# 3_NET_schdoc.net
KiCad netlist of a schematic drawn in Altium Designer
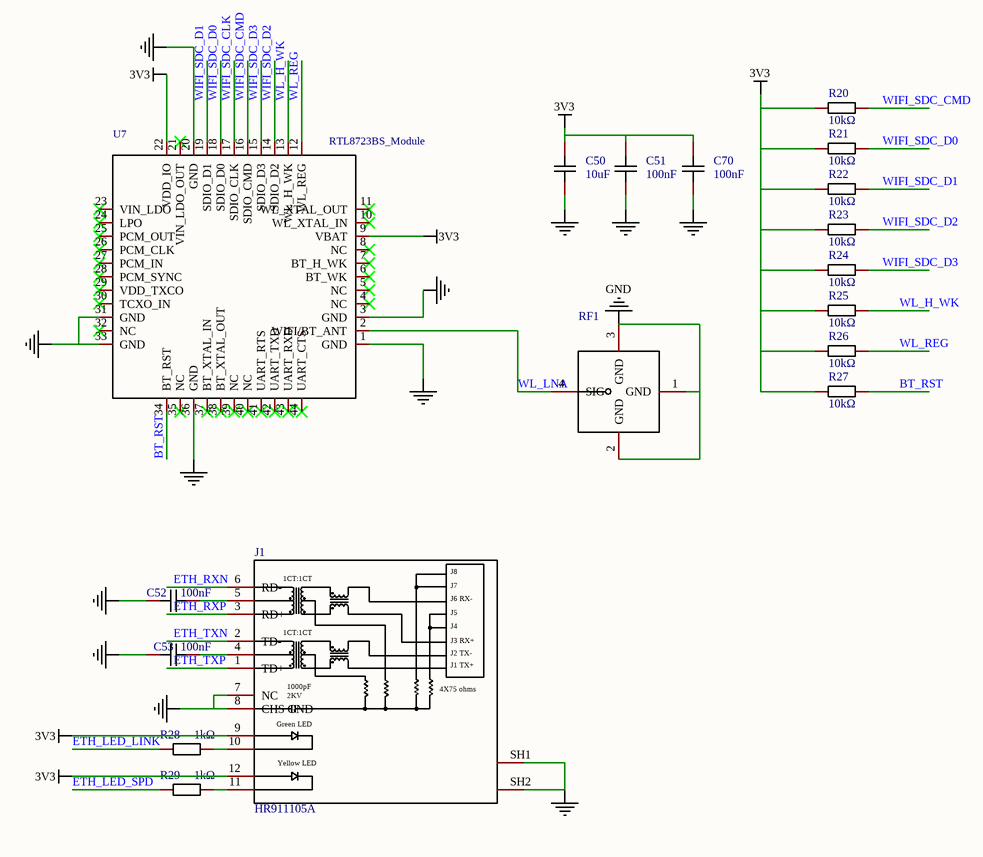
[diagram p0: 3_NET.schdoc.schdoc]

(export (version "E")
  (design (tool "Eeschema 10.0.6"))
  (components
    (comp (ref "C50")
      (value "10uF")
      (fields
        (field (name "NAME") "10uF")
        (field (name "MANUFACTURER") "SAMSUNG(三星)")
        (field (name "MANUFACTURER PART") "CL10A106KP8NNNC")
        (field (name "TOLERANCE") "±10%")
      )
      (libsource (lib "altium-import") (part "root_1_CL10A106KP8NNNC_"))
    )
    (comp (ref "C51")
      (value "100nF")
      (fields
        (field (name "NAME") "100nF")
        (field (name "MANUFACTURER") "YAGEO(国巨)")
        (field (name "MANUFACTURER PART") "CC0603KRX7R9BB104")
        (field (name "TOLERANCE") "±10%")
      )
      (libsource (lib "altium-import") (part "root_1_CC0603KRX7R9BB104_"))
    )
    (comp (ref "C52")
      (value "100nF")
      (fields
        (field (name "NAME") "100nF")
        (field (name "MANUFACTURER") "YAGEO(国巨)")
        (field (name "MANUFACTURER PART") "CC0603KRX7R9BB104")
        (field (name "TOLERANCE") "±10%")
      )
      (libsource (lib "altium-import") (part "root_0_CC0603KRX7R9BB104_"))
    )
    (comp (ref "C53")
      (value "100nF")
      (fields
        (field (name "NAME") "100nF")
        (field (name "MANUFACTURER") "YAGEO(国巨)")
        (field (name "MANUFACTURER PART") "CC0603KRX7R9BB104")
        (field (name "TOLERANCE") "±10%")
      )
      (libsource (lib "altium-import") (part "root_0_CC0603KRX7R9BB104_"))
    )
    (comp (ref "C70")
      (value "100nF")
      (fields
        (field (name "NAME") "100nF")
        (field (name "MANUFACTURER") "YAGEO(国巨)")
        (field (name "MANUFACTURER PART") "CC0603KRX7R9BB104")
        (field (name "TOLERANCE") "±10%")
      )
      (libsource (lib "altium-import") (part "root_1_CC0603KRX7R9BB104_"))
    )
    (comp (ref "J1")
      (value "HR911105A")
      (description "连接器类型:RJ插座;USOC代码:RJ45;端口数量:1;等级:-;屏蔽:-;LED:带LED;")
      (fields (field (name "NAME") "HR911105A") (field (name "MANUFACTURER") "HANRUN(汉仁)"))
      (libsource (lib "altium-import") (part "root_0_HR911105A_C12074_"))
    )
    (comp (ref "R20")
      (value "10kΩ")
      (fields
        (field (name "NAME") "10kΩ")
        (field (name "MANUFACTURER") "UNI-ROYAL(厚声)")
        (field (name "MANUFACTURER PART") "0603WAF1002T5E")
        (field (name "TOLERANCE") "±1%")
      )
      (libsource (lib "altium-import") (part "root_2_0603WAF1002T5E_"))
    )
    (comp (ref "R21")
      (value "10kΩ")
      (fields
        (field (name "NAME") "10kΩ")
        (field (name "MANUFACTURER") "UNI-ROYAL(厚声)")
        (field (name "MANUFACTURER PART") "0603WAF1002T5E")
        (field (name "TOLERANCE") "±1%")
      )
      (libsource (lib "altium-import") (part "root_2_0603WAF1002T5E_"))
    )
    (comp (ref "R22")
      (value "10kΩ")
      (fields
        (field (name "NAME") "10kΩ")
        (field (name "MANUFACTURER") "UNI-ROYAL(厚声)")
        (field (name "MANUFACTURER PART") "0603WAF1002T5E")
        (field (name "TOLERANCE") "±1%")
      )
      (libsource (lib "altium-import") (part "root_2_0603WAF1002T5E_"))
    )
    (comp (ref "R23")
      (value "10kΩ")
      (fields
        (field (name "NAME") "10kΩ")
        (field (name "MANUFACTURER") "UNI-ROYAL(厚声)")
        (field (name "MANUFACTURER PART") "0603WAF1002T5E")
        (field (name "TOLERANCE") "±1%")
      )
      (libsource (lib "altium-import") (part "root_2_0603WAF1002T5E_"))
    )
    (comp (ref "R24")
      (value "10kΩ")
      (fields
        (field (name "NAME") "10kΩ")
        (field (name "MANUFACTURER") "UNI-ROYAL(厚声)")
        (field (name "MANUFACTURER PART") "0603WAF1002T5E")
        (field (name "TOLERANCE") "±1%")
      )
      (libsource (lib "altium-import") (part "root_2_0603WAF1002T5E_"))
    )
    (comp (ref "R25")
      (value "10kΩ")
      (fields
        (field (name "NAME") "10kΩ")
        (field (name "MANUFACTURER") "UNI-ROYAL(厚声)")
        (field (name "MANUFACTURER PART") "0603WAF1002T5E")
        (field (name "TOLERANCE") "±1%")
      )
      (libsource (lib "altium-import") (part "root_2_0603WAF1002T5E_"))
    )
    (comp (ref "R26")
      (value "10kΩ")
      (fields
        (field (name "NAME") "10kΩ")
        (field (name "MANUFACTURER") "UNI-ROYAL(厚声)")
        (field (name "MANUFACTURER PART") "0603WAF1002T5E")
        (field (name "TOLERANCE") "±1%")
      )
      (libsource (lib "altium-import") (part "root_2_0603WAF1002T5E_"))
    )
    (comp (ref "R27")
      (value "10kΩ")
      (fields
        (field (name "NAME") "10kΩ")
        (field (name "MANUFACTURER") "UNI-ROYAL(厚声)")
        (field (name "MANUFACTURER PART") "0603WAF1002T5E")
        (field (name "TOLERANCE") "±1%")
      )
      (libsource (lib "altium-import") (part "root_2_0603WAF1002T5E_"))
    )
    (comp (ref "R28")
      (value "1kΩ")
      (fields
        (field (name "NAME") "1kΩ")
        (field (name "MANUFACTURER") "UNI-ROYAL(厚声)")
        (field (name "MANUFACTURER PART") "0603WAF1001T5E")
        (field (name "TOLERANCE") "±1%")
      )
      (libsource (lib "altium-import") (part "root_0_0603WAF1001T5E_"))
    )
    (comp (ref "R29")
      (value "1kΩ")
      (fields
        (field (name "NAME") "1kΩ")
        (field (name "MANUFACTURER") "UNI-ROYAL(厚声)")
        (field (name "MANUFACTURER PART") "0603WAF1001T5E")
        (field (name "TOLERANCE") "±1%")
      )
      (libsource (lib "altium-import") (part "root_0_0603WAF1001T5E_"))
    )
    (comp (ref "RF1")
      (value "KH-IPEX-K501-29")
      (description "连接器类型:板端;射频系列:IPEX;接口类型:内针;端口数量:1;阻抗:50Ω;频率-最大值:3GHz;样式:-;接口直径:2mm;接口长度/高度:1.25mm;工作温度范围:-40~+90;")
      (fields (field (name "MANUFACTURER") "kinghelm(金航标)"))
      (libsource (lib "altium-import") (part "root_1_KH-IPEX-K501-29_"))
    )
    (comp (ref "U7")
      (value "RTL8723BS_Module")
      (fields (field (name "NAME") "RTL8723BS_Module"))
      (libsource (lib "altium-import") (part "root_2_R8723BS_"))
    )
  )
  (nets
    (net (code "1") (name "/BT_RST") (class "Default")
      (node (ref "R27") (pin "1") (pinfunction "1_1") (pintype "passive"))
      (node (ref "U7") (pin "34") (pinfunction "BT_RST_34") (pintype "passive"))
    )
    (net (code "2") (name "/ETH_LED_LINK") (class "Default")
      (node (ref "R28") (pin "1") (pinfunction "1_1") (pintype "passive"))
    )
    (net (code "3") (name "/ETH_LED_SPD") (class "Default")
      (node (ref "R29") (pin "1") (pinfunction "1_1") (pintype "passive"))
    )
    (net (code "4") (name "/ETH_RXN") (class "Default")
      (node (ref "J1") (pin "6") (pinfunction "RD-_6") (pintype "passive"))
    )
    (net (code "5") (name "/ETH_RXP") (class "Default")
      (node (ref "J1") (pin "3") (pinfunction "RD+_3") (pintype "passive"))
    )
    (net (code "6") (name "/ETH_TXN") (class "Default")
      (node (ref "J1") (pin "2") (pinfunction "TD-_2") (pintype "passive"))
    )
    (net (code "7") (name "/ETH_TXP") (class "Default")
      (node (ref "J1") (pin "1") (pinfunction "TD+_1") (pintype "passive"))
    )
    (net (code "8") (name "/WIFI_SDC_CLK") (class "Default")
      (node (ref "U7") (pin "17") (pinfunction "SDIO_CLK_17") (pintype "passive"))
    )
    (net (code "9") (name "/WIFI_SDC_CMD") (class "Default")
      (node (ref "R20") (pin "1") (pinfunction "1_1") (pintype "passive"))
      (node (ref "U7") (pin "16") (pinfunction "SDIO_CMD_16") (pintype "passive"))
    )
    (net (code "10") (name "/WIFI_SDC_D0") (class "Default")
      (node (ref "R21") (pin "1") (pinfunction "1_1") (pintype "passive"))
      (node (ref "U7") (pin "18") (pinfunction "SDIO_D0_18") (pintype "passive"))
    )
    (net (code "11") (name "/WIFI_SDC_D1") (class "Default")
      (node (ref "R22") (pin "1") (pinfunction "1_1") (pintype "passive"))
      (node (ref "U7") (pin "19") (pinfunction "SDIO_D1_19") (pintype "passive"))
    )
    (net (code "12") (name "/WIFI_SDC_D2") (class "Default")
      (node (ref "R23") (pin "1") (pinfunction "1_1") (pintype "passive"))
      (node (ref "U7") (pin "14") (pinfunction "SDIO_D2_14") (pintype "passive"))
    )
    (net (code "13") (name "/WIFI_SDC_D3") (class "Default")
      (node (ref "R24") (pin "1") (pinfunction "1_1") (pintype "passive"))
      (node (ref "U7") (pin "15") (pinfunction "SDIO_D3_15") (pintype "passive"))
    )
    (net (code "14") (name "/WL_H_WK") (class "Default")
      (node (ref "R25") (pin "1") (pinfunction "1_1") (pintype "passive"))
      (node (ref "U7") (pin "13") (pinfunction "WL_H_WK_13") (pintype "passive"))
    )
    (net (code "15") (name "/WL_LNA") (class "Default")
      (node (ref "RF1") (pin "4") (pinfunction "SIG_4") (pintype "passive"))
      (node (ref "U7") (pin "2") (pinfunction "WIFI/BT_ANT_2") (pintype "passive"))
    )
    (net (code "16") (name "/WL_REG") (class "Default")
      (node (ref "R26") (pin "1") (pinfunction "1_1") (pintype "passive"))
      (node (ref "U7") (pin "12") (pinfunction "WL_REG_12") (pintype "passive"))
    )
    (net (code "17") (name "3V3") (class "Default")
      (node (ref "C50") (pin "2") (pinfunction "2_2") (pintype "passive"))
      (node (ref "C51") (pin "2") (pinfunction "2_2") (pintype "passive"))
      (node (ref "C70") (pin "2") (pinfunction "2_2") (pintype "passive"))
      (node (ref "J1") (pin "12") (pinfunction "12_12") (pintype "passive"))
      (node (ref "J1") (pin "9") (pinfunction "9_9") (pintype "passive"))
      (node (ref "R20") (pin "2") (pinfunction "2_2") (pintype "passive"))
      (node (ref "R21") (pin "2") (pinfunction "2_2") (pintype "passive"))
      (node (ref "R22") (pin "2") (pinfunction "2_2") (pintype "passive"))
      (node (ref "R23") (pin "2") (pinfunction "2_2") (pintype "passive"))
      (node (ref "R24") (pin "2") (pinfunction "2_2") (pintype "passive"))
      (node (ref "R25") (pin "2") (pinfunction "2_2") (pintype "passive"))
      (node (ref "R26") (pin "2") (pinfunction "2_2") (pintype "passive"))
      (node (ref "R27") (pin "2") (pinfunction "2_2") (pintype "passive"))
      (node (ref "U7") (pin "22") (pinfunction "VDD_IO_22") (pintype "passive"))
      (node (ref "U7") (pin "9") (pinfunction "VBAT_9") (pintype "passive"))
    )
    (net (code "18") (name "<NO NET>") (class "Default")
      (node (ref "C50") (pin "1") (pinfunction "1_1") (pintype "passive"))
      (node (ref "C51") (pin "1") (pinfunction "1_1") (pintype "passive"))
      (node (ref "C52") (pin "1") (pinfunction "1_1") (pintype "passive"))
      (node (ref "C53") (pin "1") (pinfunction "1_1") (pintype "passive"))
      (node (ref "C70") (pin "1") (pinfunction "1_1") (pintype "passive"))
      (node (ref "J1") (pin "7") (pinfunction "NC_7") (pintype "passive"))
      (node (ref "J1") (pin "8") (pinfunction "CHS_GND_8") (pintype "passive"))
      (node (ref "J1") (pin "SH1") (pinfunction "SH1_SH1") (pintype "passive"))
      (node (ref "J1") (pin "SH2") (pinfunction "SH2_SH2") (pintype "passive"))
      (node (ref "U7") (pin "1") (pinfunction "GND_1") (pintype "passive"))
      (node (ref "U7") (pin "20") (pinfunction "GND_20") (pintype "passive"))
      (node (ref "U7") (pin "3") (pinfunction "GND_3") (pintype "passive"))
      (node (ref "U7") (pin "31") (pinfunction "GND_31") (pintype "passive"))
      (node (ref "U7") (pin "33") (pinfunction "GND_33") (pintype "passive"))
      (node (ref "U7") (pin "36") (pinfunction "GND_36") (pintype "passive"))
    )
    (net (code "19") (name "GND") (class "Default")
      (node (ref "RF1") (pin "1") (pinfunction "GND_1") (pintype "passive"))
      (node (ref "RF1") (pin "2") (pinfunction "GND_2") (pintype "passive"))
      (node (ref "RF1") (pin "3") (pinfunction "GND_3") (pintype "passive"))
    )
    (net (code "20") (name "Net-(C52-Pad2)") (class "Default")
      (node (ref "C52") (pin "2") (pinfunction "2_2") (pintype "passive"))
      (node (ref "J1") (pin "5") (pinfunction "5_5") (pintype "passive"))
    )
    (net (code "21") (name "Net-(C53-Pad2)") (class "Default")
      (node (ref "C53") (pin "2") (pinfunction "2_2") (pintype "passive"))
      (node (ref "J1") (pin "4") (pinfunction "4_4") (pintype "passive"))
    )
    (net (code "22") (name "Net-(J1-Pad10)") (class "Default")
      (node (ref "J1") (pin "10") (pinfunction "10_10") (pintype "passive"))
      (node (ref "R28") (pin "2") (pinfunction "2_2") (pintype "passive"))
    )
    (net (code "23") (name "Net-(J1-Pad11)") (class "Default")
      (node (ref "J1") (pin "11") (pinfunction "11_11") (pintype "passive"))
      (node (ref "R29") (pin "2") (pinfunction "2_2") (pintype "passive"))
    )
    (net (code "24") (name "unconnected-(U7-BT_H_WK-Pad7)") (class "Default")
      (node (ref "U7") (pin "7") (pinfunction "BT_H_WK_7") (pintype "passive+no_connect"))
    )
    (net (code "25") (name "unconnected-(U7-BT_WK-Pad6)") (class "Default")
      (node (ref "U7") (pin "6") (pinfunction "BT_WK_6") (pintype "passive+no_connect"))
    )
    (net (code "26") (name "unconnected-(U7-BT_XTAL_IN-Pad37)") (class "Default")
      (node (ref "U7") (pin "37") (pinfunction "BT_XTAL_IN_37") (pintype "passive+no_connect"))
    )
    (net (code "27") (name "unconnected-(U7-BT_XTAL_OUT-Pad38)") (class "Default")
      (node (ref "U7") (pin "38") (pinfunction "BT_XTAL_OUT_38") (pintype "passive+no_connect"))
    )
    (net (code "28") (name "unconnected-(U7-LPO-Pad24)") (class "Default")
      (node (ref "U7") (pin "24") (pinfunction "LPO_24") (pintype "passive+no_connect"))
    )
    (net (code "29") (name "unconnected-(U7-NC-Pad4)") (class "Default")
      (node (ref "U7") (pin "4") (pinfunction "NC_4") (pintype "passive+no_connect"))
    )
    (net (code "30") (name "unconnected-(U7-NC-Pad5)") (class "Default")
      (node (ref "U7") (pin "5") (pinfunction "NC_5") (pintype "passive+no_connect"))
    )
    (net (code "31") (name "unconnected-(U7-NC-Pad8)") (class "Default")
      (node (ref "U7") (pin "8") (pinfunction "NC_8") (pintype "passive+no_connect"))
    )
    (net (code "32") (name "unconnected-(U7-NC-Pad32)") (class "Default")
      (node (ref "U7") (pin "32") (pinfunction "NC_32") (pintype "passive+no_connect"))
    )
    (net (code "33") (name "unconnected-(U7-NC-Pad35)") (class "Default")
      (node (ref "U7") (pin "35") (pinfunction "NC_35") (pintype "passive+no_connect"))
    )
    (net (code "34") (name "unconnected-(U7-NC-Pad39)") (class "Default")
      (node (ref "U7") (pin "39") (pinfunction "NC_39") (pintype "passive+no_connect"))
    )
    (net (code "35") (name "unconnected-(U7-NC-Pad40)") (class "Default")
      (node (ref "U7") (pin "40") (pinfunction "NC_40") (pintype "passive+no_connect"))
    )
    (net (code "36") (name "unconnected-(U7-PCM_CLK-Pad26)") (class "Default")
      (node (ref "U7") (pin "26") (pinfunction "PCM_CLK_26") (pintype "passive+no_connect"))
    )
    (net (code "37") (name "unconnected-(U7-PCM_IN-Pad27)") (class "Default")
      (node (ref "U7") (pin "27") (pinfunction "PCM_IN_27") (pintype "passive+no_connect"))
    )
    (net (code "38") (name "unconnected-(U7-PCM_OUT-Pad25)") (class "Default")
      (node (ref "U7") (pin "25") (pinfunction "PCM_OUT_25") (pintype "passive+no_connect"))
    )
    (net (code "39") (name "unconnected-(U7-PCM_SYNC-Pad28)") (class "Default")
      (node (ref "U7") (pin "28") (pinfunction "PCM_SYNC_28") (pintype "passive+no_connect"))
    )
    (net (code "40") (name "unconnected-(U7-TCXO_IN-Pad30)") (class "Default")
      (node (ref "U7") (pin "30") (pinfunction "TCXO_IN_30") (pintype "passive+no_connect"))
    )
    (net (code "41") (name "unconnected-(U7-UART_CTS-Pad44)") (class "Default")
      (node (ref "U7") (pin "44") (pinfunction "UART_CTS_44") (pintype "passive+no_connect"))
    )
    (net (code "42") (name "unconnected-(U7-UART_RTS-Pad41)") (class "Default")
      (node (ref "U7") (pin "41") (pinfunction "UART_RTS_41") (pintype "passive+no_connect"))
    )
    (net (code "43") (name "unconnected-(U7-UART_RXD-Pad43)") (class "Default")
      (node (ref "U7") (pin "43") (pinfunction "UART_RXD_43") (pintype "passive+no_connect"))
    )
    (net (code "44") (name "unconnected-(U7-UART_TXD-Pad42)") (class "Default")
      (node (ref "U7") (pin "42") (pinfunction "UART_TXD_42") (pintype "passive+no_connect"))
    )
    (net (code "45") (name "unconnected-(U7-VDD_TXCO-Pad29)") (class "Default")
      (node (ref "U7") (pin "29") (pinfunction "VDD_TXCO_29") (pintype "passive+no_connect"))
    )
    (net (code "46") (name "unconnected-(U7-VIN_LDO-Pad23)") (class "Default")
      (node (ref "U7") (pin "23") (pinfunction "VIN_LDO_23") (pintype "passive+no_connect"))
    )
    (net (code "47") (name "unconnected-(U7-VIN_LDO_OUT-Pad21)") (class "Default")
      (node (ref "U7") (pin "21") (pinfunction "VIN_LDO_OUT_21") (pintype "passive+no_connect"))
    )
    (net (code "48") (name "unconnected-(U7-WL_XTAL_IN-Pad10)") (class "Default")
      (node (ref "U7") (pin "10") (pinfunction "WL_XTAL_IN_10") (pintype "passive+no_connect"))
    )
    (net (code "49") (name "unconnected-(U7-WL_XTAL_OUT-Pad11)") (class "Default")
      (node (ref "U7") (pin "11") (pinfunction "WL_XTAL_OUT_11") (pintype "passive+no_connect"))
    )
  )
)
